# vssb_324.net
KiCad netlist of a schematic drawn in EAGLE
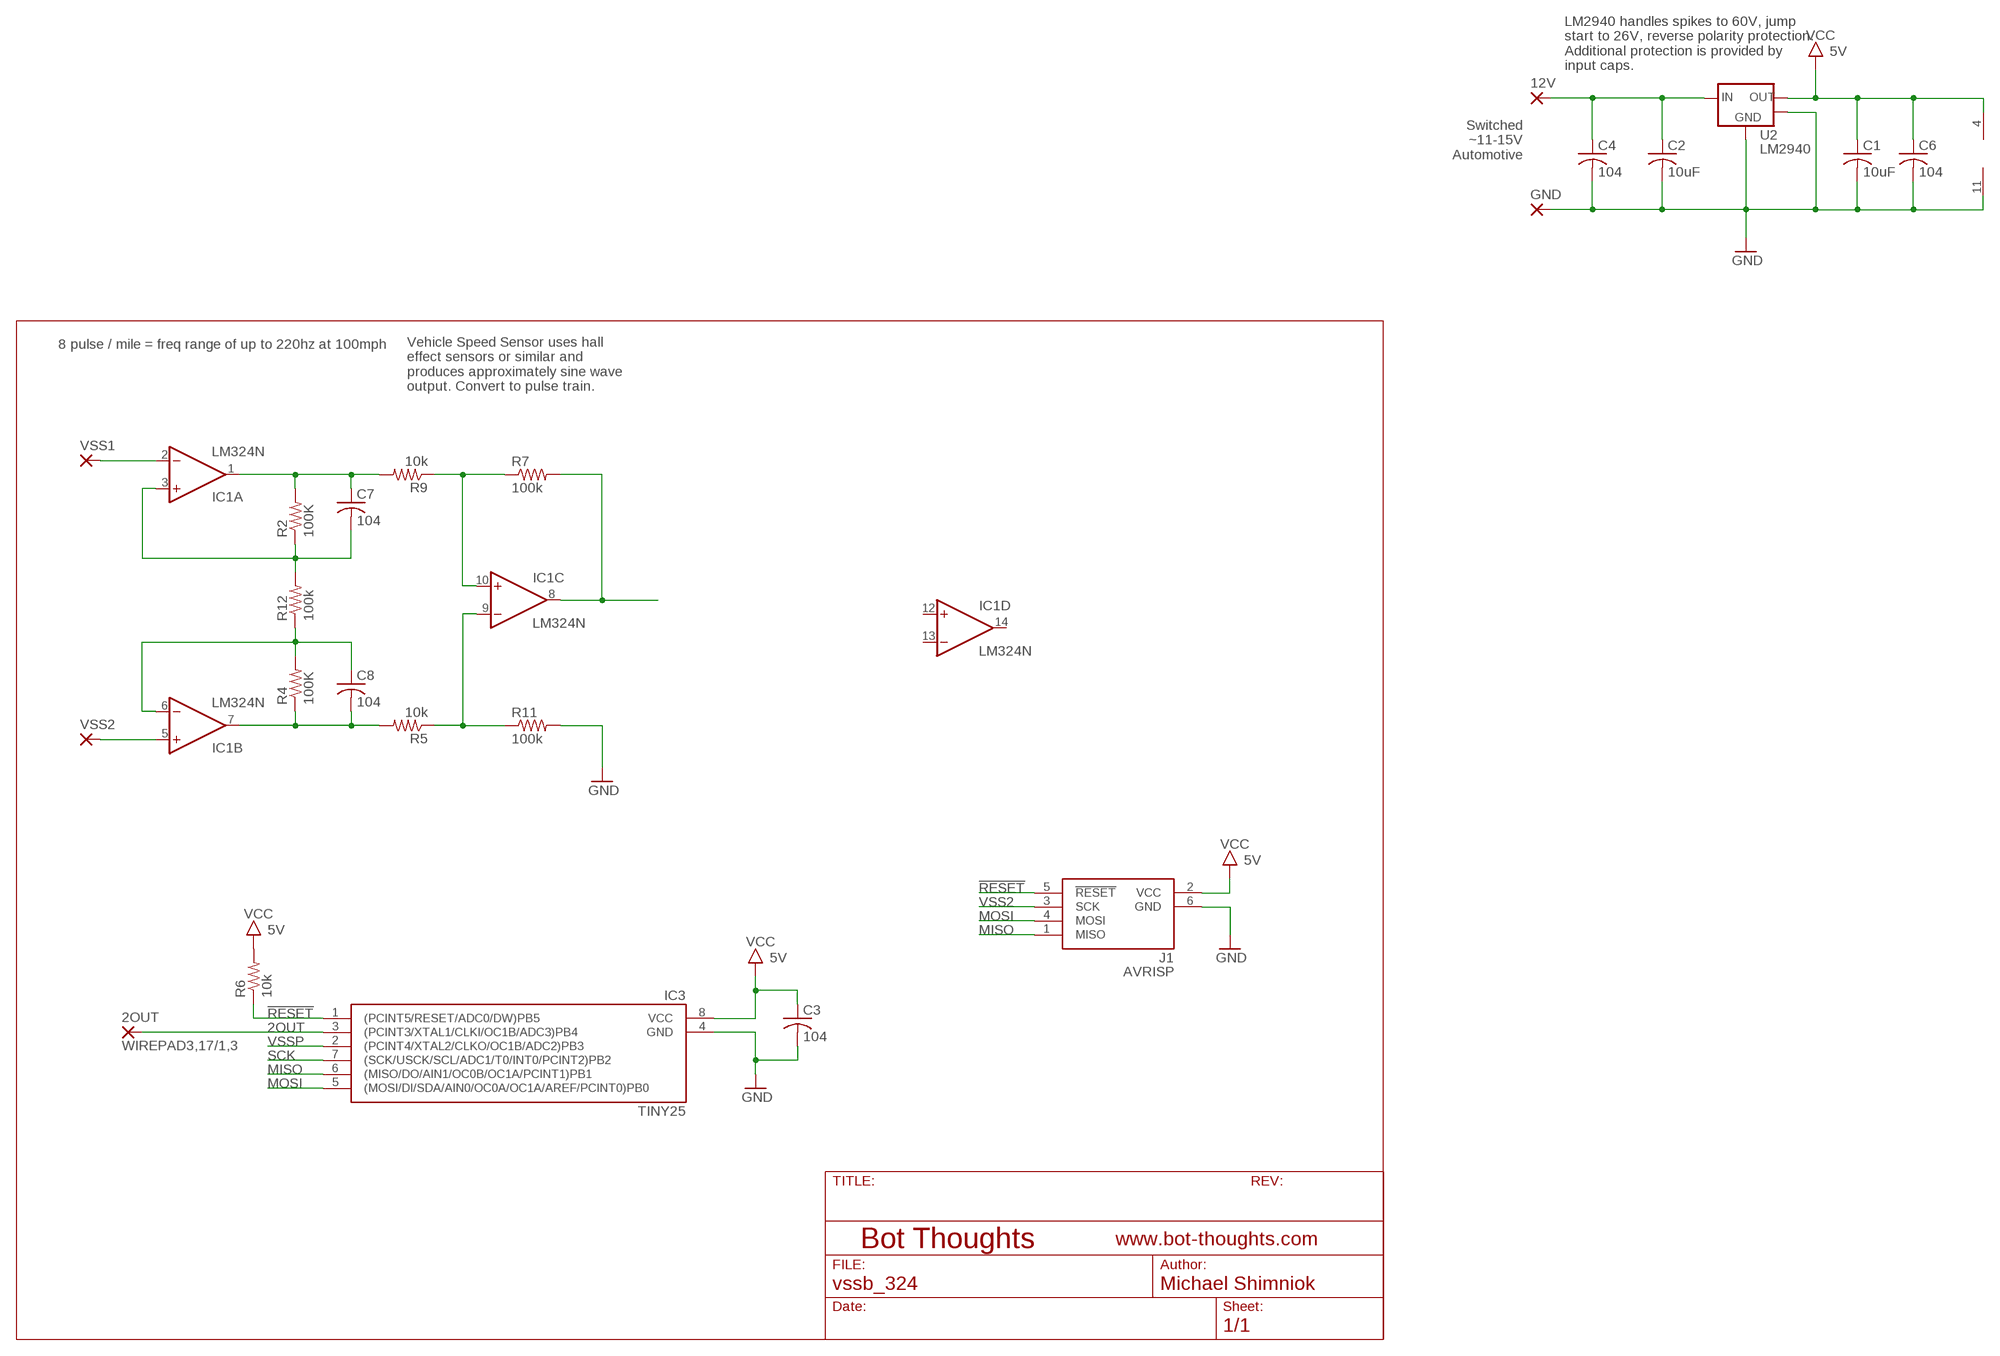
[diagram p0: schematic, sheet 1]

(export (version "E")
  (design (tool "Eeschema 10.0.6"))
  (components
    (comp (ref "2OUT")
      (value "WIREPAD3,17/1,3")
      (footprint "eagle-import:3,17_1,3")
      (libsource (lib "eagle-import") (part "WIREPAD3,17/1,3"))
    )
    (comp (ref "12V")
      (value "WIREPAD3,17/1,3")
      (footprint "eagle-import:3,17_1,3")
      (libsource (lib "eagle-import") (part "WIREPAD3,17/1,3"))
    )
    (comp (ref "C1")
      (value "10uF")
      (footprint "eagle-import:C1206")
      (libsource (lib "eagle-import") (part "C-USC1206"))
    )
    (comp (ref "C2")
      (value "10uF")
      (footprint "eagle-import:C1206")
      (libsource (lib "eagle-import") (part "C-USC1206"))
    )
    (comp (ref "C3")
      (value "104")
      (footprint "eagle-import:C0603")
      (libsource (lib "eagle-import") (part "C-USC0603"))
    )
    (comp (ref "C4")
      (value "104")
      (footprint "eagle-import:C0603")
      (libsource (lib "eagle-import") (part "C-USC0603"))
    )
    (comp (ref "C6")
      (value "104")
      (footprint "eagle-import:C0603")
      (libsource (lib "eagle-import") (part "C-USC0603"))
    )
    (comp (ref "C7")
      (value "104")
      (footprint "eagle-import:C0603")
      (libsource (lib "eagle-import") (part "C-USC0603"))
    )
    (comp (ref "C8")
      (value "104")
      (footprint "eagle-import:C0603")
      (libsource (lib "eagle-import") (part "C-USC0603"))
    )
    (comp (ref "GND")
      (value "WIREPAD3,17/1,3")
      (footprint "eagle-import:3,17_1,3")
      (libsource (lib "eagle-import") (part "WIREPAD3,17/1,3"))
    )
    (comp (ref "IC1")
      (value "LM324N")
      (footprint "eagle-import:DIL14")
      (libsource (lib "eagle-import") (part "LM324N"))
    )
    (comp (ref "IC3")
      (value "TINY25")
      (footprint "eagle-import:DIL08")
      (libsource (lib "eagle-import") (part "TINY25/45/85-20PU"))
    )
    (comp (ref "J1")
      (value "AVRISP")
      (footprint "eagle-import:CON6P2R")
      (libsource (lib "eagle-import") (part "AVRISP6_COMPACT"))
    )
    (comp (ref "R2")
      (value "100K")
      (footprint "eagle-import:R0603")
      (libsource (lib "eagle-import") (part "R-US_R0603"))
    )
    (comp (ref "R4")
      (value "100K")
      (footprint "eagle-import:R0603")
      (libsource (lib "eagle-import") (part "R-US_R0603"))
    )
    (comp (ref "R5")
      (value "10k")
      (footprint "eagle-import:R0603")
      (libsource (lib "eagle-import") (part "R-US_R0603"))
    )
    (comp (ref "R6")
      (value "10k")
      (footprint "eagle-import:R0603")
      (libsource (lib "eagle-import") (part "R-US_R0603"))
    )
    (comp (ref "R7")
      (value "100k")
      (footprint "eagle-import:R0603")
      (libsource (lib "eagle-import") (part "R-US_R0603"))
    )
    (comp (ref "R9")
      (value "10k")
      (footprint "eagle-import:R0603")
      (libsource (lib "eagle-import") (part "R-US_R0603"))
    )
    (comp (ref "R11")
      (value "100k")
      (footprint "eagle-import:R0603")
      (libsource (lib "eagle-import") (part "R-US_R0603"))
    )
    (comp (ref "R12")
      (value "100k")
      (footprint "eagle-import:R0603")
      (libsource (lib "eagle-import") (part "R-US_R0603"))
    )
    (comp (ref "U2")
      (value "LM2940")
      (footprint "eagle-import:TO263-3")
      (libsource (lib "eagle-import") (part "LM2940KTT"))
    )
    (comp (ref "VSS1")
      (value "WIREPAD3,17/1,3")
      (footprint "eagle-import:3,17_1,3")
      (libsource (lib "eagle-import") (part "WIREPAD3,17/1,3"))
    )
    (comp (ref "VSS2")
      (value "WIREPAD3,17/1,3")
      (footprint "eagle-import:3,17_1,3")
      (libsource (lib "eagle-import") (part "WIREPAD3,17/1,3"))
    )
  )
  (nets
    (net (code "1") (name "/2OUT") (class "Default")
      (node (ref "2OUT") (pin "1") (pinfunction "P_1") (pintype "passive"))
      (node (ref "IC3") (pin "3") (pinfunction "(PCINT3/XTAL1/CLKI/OC1B/ADC3)PB4_3") (pintype "bidirectional"))
    )
    (net (code "2") (name "/MISO") (class "Default")
      (node (ref "IC3") (pin "6") (pinfunction "(MISO/DO/AIN1/OC0B/OC1A/PCINT1)PB1_6") (pintype "bidirectional"))
      (node (ref "J1") (pin "1") (pinfunction "MISO_1") (pintype "input"))
    )
    (net (code "3") (name "/MOSI") (class "Default")
      (node (ref "IC3") (pin "5") (pinfunction "(MOSI/DI/SDA/AIN0/OC0A/OC1A/AREF/PCINT0)PB0_5") (pintype "bidirectional"))
      (node (ref "J1") (pin "4") (pinfunction "MOSI_4") (pintype "output"))
    )
    (net (code "4") (name "/SCK") (class "Default")
      (node (ref "IC3") (pin "7") (pinfunction "(SCK/USCK/SCL/ADC1/T0/INT0/PCINT2)PB2_7") (pintype "bidirectional"))
    )
    (net (code "5") (name "/VSS2") (class "Default")
      (node (ref "IC1") (pin "5") (pinfunction "+IN_5") (pintype "input"))
      (node (ref "J1") (pin "3") (pinfunction "SCK_3") (pintype "output"))
      (node (ref "VSS2") (pin "1") (pinfunction "P_1") (pintype "passive"))
    )
    (net (code "6") (name "/VSSP") (class "Default")
      (node (ref "IC3") (pin "2") (pinfunction "(PCINT4/XTAL2/CLKO/OC1B/ADC2)PB3_2") (pintype "bidirectional"))
    )
    (net (code "7") (name "/~{RESET}") (class "Default")
      (node (ref "IC3") (pin "1") (pinfunction "(PCINT5/RESET/ADC0/DW)PB5_1") (pintype "bidirectional"))
      (node (ref "J1") (pin "5") (pinfunction "~{RESET}_5") (pintype "output"))
      (node (ref "R6") (pin "1") (pinfunction "1_1") (pintype "passive"))
    )
    (net (code "8") (name "5V") (class "Default")
      (node (ref "C1") (pin "1") (pinfunction "1_1") (pintype "passive"))
      (node (ref "C3") (pin "1") (pinfunction "1_1") (pintype "passive"))
      (node (ref "C6") (pin "1") (pinfunction "1_1") (pintype "passive"))
      (node (ref "IC1") (pin "4") (pinfunction "V+_4") (pintype "power_in"))
      (node (ref "IC3") (pin "8") (pinfunction "VCC_8") (pintype "power_in"))
      (node (ref "J1") (pin "2") (pinfunction "VCC_2") (pintype "power_in"))
      (node (ref "R6") (pin "2") (pinfunction "2_2") (pintype "passive"))
      (node (ref "U2") (pin "3") (pinfunction "VOUT_3") (pintype "bidirectional"))
    )
    (net (code "9") (name "GND") (class "Default")
      (node (ref "C1") (pin "2") (pinfunction "2_2") (pintype "passive"))
      (node (ref "C2") (pin "2") (pinfunction "2_2") (pintype "passive"))
      (node (ref "C3") (pin "2") (pinfunction "2_2") (pintype "passive"))
      (node (ref "C4") (pin "2") (pinfunction "2_2") (pintype "passive"))
      (node (ref "C6") (pin "2") (pinfunction "2_2") (pintype "passive"))
      (node (ref "GND") (pin "1") (pinfunction "P_1") (pintype "passive"))
      (node (ref "IC1") (pin "11") (pinfunction "V-_11") (pintype "power_in"))
      (node (ref "IC3") (pin "4") (pinfunction "GND_4") (pintype "power_in"))
      (node (ref "J1") (pin "6") (pinfunction "GND_6") (pintype "power_in"))
      (node (ref "R11") (pin "2") (pinfunction "2_2") (pintype "passive"))
      (node (ref "U2") (pin "2") (pinfunction "GND_2") (pintype "bidirectional"))
      (node (ref "U2") (pin "4") (pinfunction "TAB_4") (pintype "bidirectional"))
    )
    (net (code "10") (name "Net-(12V-P)") (class "Default")
      (node (ref "12V") (pin "1") (pinfunction "P_1") (pintype "passive"))
      (node (ref "C2") (pin "1") (pinfunction "1_1") (pintype "passive"))
      (node (ref "C4") (pin "1") (pinfunction "1_1") (pintype "passive"))
      (node (ref "U2") (pin "1") (pinfunction "VIN_1") (pintype "bidirectional"))
    )
    (net (code "11") (name "Net-(IC1A-+IN)") (class "Default")
      (node (ref "C7") (pin "2") (pinfunction "2_2") (pintype "passive"))
      (node (ref "IC1") (pin "3") (pinfunction "+IN_3") (pintype "input"))
      (node (ref "R12") (pin "2") (pinfunction "2_2") (pintype "passive"))
      (node (ref "R2") (pin "1") (pinfunction "1_1") (pintype "passive"))
    )
    (net (code "12") (name "Net-(IC1A--IN)") (class "Default")
      (node (ref "IC1") (pin "2") (pinfunction "-IN_2") (pintype "input"))
      (node (ref "VSS1") (pin "1") (pinfunction "P_1") (pintype "passive"))
    )
    (net (code "13") (name "Net-(IC1A-OUT)") (class "Default")
      (node (ref "C7") (pin "1") (pinfunction "1_1") (pintype "passive"))
      (node (ref "IC1") (pin "1") (pinfunction "OUT_1") (pintype "output"))
      (node (ref "R2") (pin "2") (pinfunction "2_2") (pintype "passive"))
      (node (ref "R9") (pin "2") (pinfunction "2_2") (pintype "passive"))
    )
    (net (code "14") (name "Net-(IC1B--IN)") (class "Default")
      (node (ref "C8") (pin "1") (pinfunction "1_1") (pintype "passive"))
      (node (ref "IC1") (pin "6") (pinfunction "-IN_6") (pintype "input"))
      (node (ref "R12") (pin "1") (pinfunction "1_1") (pintype "passive"))
      (node (ref "R4") (pin "2") (pinfunction "2_2") (pintype "passive"))
    )
    (net (code "15") (name "Net-(IC1B-OUT)") (class "Default")
      (node (ref "C8") (pin "2") (pinfunction "2_2") (pintype "passive"))
      (node (ref "IC1") (pin "7") (pinfunction "OUT_7") (pintype "output"))
      (node (ref "R4") (pin "1") (pinfunction "1_1") (pintype "passive"))
      (node (ref "R5") (pin "2") (pinfunction "2_2") (pintype "passive"))
    )
    (net (code "16") (name "Net-(IC1C-+IN)") (class "Default")
      (node (ref "IC1") (pin "10") (pinfunction "+IN_10") (pintype "input"))
      (node (ref "R7") (pin "1") (pinfunction "1_1") (pintype "passive"))
      (node (ref "R9") (pin "1") (pinfunction "1_1") (pintype "passive"))
    )
    (net (code "17") (name "Net-(IC1C--IN)") (class "Default")
      (node (ref "IC1") (pin "9") (pinfunction "-IN_9") (pintype "input"))
      (node (ref "R11") (pin "1") (pinfunction "1_1") (pintype "passive"))
      (node (ref "R5") (pin "1") (pinfunction "1_1") (pintype "passive"))
    )
    (net (code "18") (name "Net-(IC1C-OUT)") (class "Default")
      (node (ref "IC1") (pin "8") (pinfunction "OUT_8") (pintype "output"))
      (node (ref "R7") (pin "2") (pinfunction "2_2") (pintype "passive"))
    )
    (net (code "19") (name "unconnected-(IC1D-+IN-Pad12)") (class "Default")
      (node (ref "IC1") (pin "12") (pinfunction "+IN_12") (pintype "input"))
    )
    (net (code "20") (name "unconnected-(IC1D--IN-Pad13)") (class "Default")
      (node (ref "IC1") (pin "13") (pinfunction "-IN_13") (pintype "input"))
    )
    (net (code "21") (name "unconnected-(IC1D-OUT-Pad14)") (class "Default")
      (node (ref "IC1") (pin "14") (pinfunction "OUT_14") (pintype "output"))
    )
  )
)
